# Power.net
KiCad netlist of a schematic drawn in Altium Designer
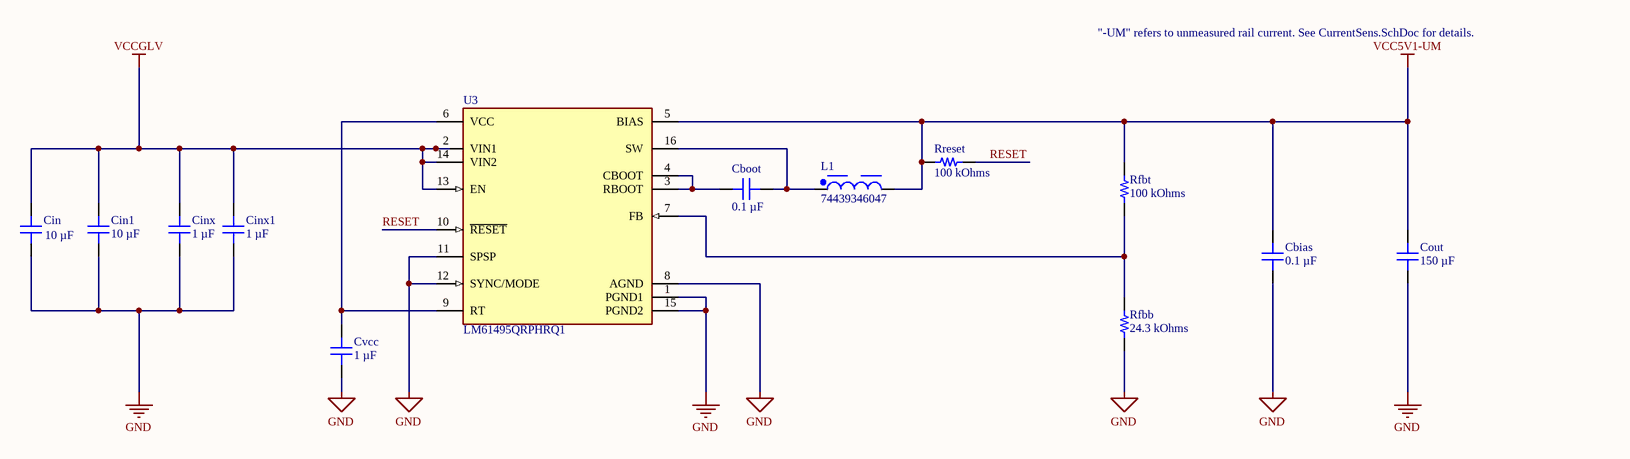
[diagram p0: Power.SchDoc]

(export (version "E")
  (design (tool "Eeschema 10.0.6"))
  (components
    (comp (ref "Cbias")
      (value "0.1 µF")
      (footprint "CAP 0402_1005")
      (description "CAP CER 0.1UF 16V X7R 0402")
      (fields
        (field (name "PART NUMBER") "CL05B104KO5NFNC")
        (field (name "MANUFACTURER") "Samsung Electro-Mechanics")
      )
      (libsource (lib "Celestial Altium Library - altium_library") (part "Capacitor"))
    )
    (comp (ref "Cboot")
      (value "0.1 µF")
      (footprint "CAP 0402_1005")
      (description "CAP CER 0.1UF 10V X7R 0402")
      (fields
        (field (name "PART NUMBER") "CL05B104KP5NNNC")
        (field (name "MANUFACTURER") "Samsung Electro-Mechanics")
      )
      (libsource (lib "Celestial Altium Library - altium_library") (part "Capacitor"))
    )
    (comp (ref "Cin")
      (value "10 µF")
      (footprint "CAP 1210_3225 - 1MM")
      (description "CAP CER 10UF 50V X7R 1210")
      (fields
        (field (name "PART NUMBER") "GRM32ER71H106KA12L")
        (field (name "MANUFACTURER") "Murata Electronics")
      )
      (libsource (lib "Celestial Altium Library - altium_library") (part "Capacitor"))
    )
    (comp (ref "Cin1")
      (value "10 µF")
      (footprint "CAP 1210_3225 - 1MM")
      (description "CAP CER 10UF 50V X7R 1210")
      (fields
        (field (name "PART NUMBER") "GRM32ER71H106KA12L")
        (field (name "MANUFACTURER") "Murata Electronics")
      )
      (libsource (lib "Celestial Altium Library - altium_library") (part "Capacitor"))
    )
    (comp (ref "Cinx")
      (value "1 µF")
      (footprint "CAP 0603_1608")
      (description "CAP CER 1UF 50V X5R 0603")
      (fields
        (field (name "PART NUMBER") "C1608X5R1H105K080AB")
        (field (name "MANUFACTURER") "TDK Corporation")
      )
      (libsource (lib "Celestial Altium Library - altium_library") (part "Capacitor"))
    )
    (comp (ref "Cinx1")
      (value "1 µF")
      (footprint "CAP 0603_1608")
      (description "CAP CER 1UF 50V X5R 0603")
      (fields
        (field (name "PART NUMBER") "C1608X5R1H105K080AB")
        (field (name "MANUFACTURER") "TDK Corporation")
      )
      (libsource (lib "Celestial Altium Library - altium_library") (part "Capacitor"))
    )
    (comp (ref "Cout")
      (value "150 µF")
      (footprint "CAP 1210_3225 - 1MM")
      (description "CAP CER 150UF 6.3V X5R 1210")
      (fields
        (field (name "PART NUMBER") "CL32A157MQVNNNE")
        (field (name "MANUFACTURER") "Samsung Electro-Mechanics")
      )
      (libsource (lib "Celestial Altium Library - altium_library") (part "Capacitor"))
    )
    (comp (ref "Cvcc")
      (value "1 µF")
      (footprint "CAP 0603_1608")
      (description "CAP CER 1UF 6.3V X5R 0603")
      (fields (field (name "PART NUMBER") "KGM15BR50J105KT") (field (name "MANUFACTURER") "KYOCERA AVX"))
      (libsource (lib "Celestial Altium Library - altium_library") (part "Capacitor"))
    )
    (comp (ref "L1")
      (value "74439346047")
      (footprint "WE-XHMI_6060_L6.65W6.45H5.8")
      (description "FIXED IND 4.7UH 7.4A 13 MOHM")
      (fields (field (name "TOLERANCE") "20%"))
      (libsource (lib "Altium Content Vault") (part "Inductor - 2"))
    )
    (comp (ref "Rfbb")
      (value "24.3 kOhms")
      (footprint "RES 0402_1005")
      (description "RES SMD 24.3K OHM 1% 1/16W 0402")
      (fields (field (name "PART NUMBER") "CRCW040224K3FKTD") (field (name "MANUFACTURER") "Vishay Dale"))
      (libsource (lib "Celestial Altium Library - altium_library") (part "Resistor"))
    )
    (comp (ref "Rfbt")
      (value "100 kOhms")
      (footprint "RES 0402_1005")
      (description "RES SMD 100K OHM 1% 1/16W 0402")
      (fields (field (name "PART NUMBER") "CRCW0402100KFKED") (field (name "MANUFACTURER") "Vishay Dale"))
      (libsource (lib "Celestial Altium Library - altium_library") (part "Resistor"))
    )
    (comp (ref "Rreset")
      (value "100 kOhms")
      (footprint "RES 0402_1005")
      (description "RES SMD 100K OHM 1% 1/16W 0402")
      (fields (field (name "PART NUMBER") "CRCW0402100KFKED") (field (name "MANUFACTURER") "Vishay Dale"))
      (libsource (lib "Celestial Altium Library - altium_library") (part "Resistor"))
    )
    (comp (ref "U3")
      (value "LM61495QRPHRQ1")
      (footprint "FP-RPH0016A-MFG")
      (description "10-A automotive buck converter optimized for power density and low EMI 16-VQFN-HR -40 to 150")
      (libsource (lib "Altium Content Vault") (part "31ba6acbc2ffca682b30009bfb1cfc4"))
    )
  )
  (nets
    (net (code "1") (name "/RESET") (class "Default")
      (node (ref "Rreset") (pin "2") (pinfunction "2_2") (pintype "passive"))
      (node (ref "U3") (pin "10") (pinfunction "~{RESET}_10") (pintype "input"))
    )
    (net (code "2") (name "GND") (class "Default")
      (node (ref "Cbias") (pin "1") (pinfunction "1_1") (pintype "passive"))
      (node (ref "Cin") (pin "1") (pinfunction "1_1") (pintype "passive"))
      (node (ref "Cin1") (pin "1") (pinfunction "1_1") (pintype "passive"))
      (node (ref "Cinx") (pin "1") (pinfunction "1_1") (pintype "passive"))
      (node (ref "Cinx1") (pin "1") (pinfunction "1_1") (pintype "passive"))
      (node (ref "Cout") (pin "1") (pinfunction "1_1") (pintype "passive"))
      (node (ref "Cvcc") (pin "1") (pinfunction "1_1") (pintype "passive"))
      (node (ref "Rfbb") (pin "1") (pinfunction "1_1") (pintype "passive"))
      (node (ref "U3") (pin "1") (pinfunction "PGND1_1") (pintype "power_in"))
      (node (ref "U3") (pin "11") (pinfunction "SPSP_11") (pintype "passive"))
      (node (ref "U3") (pin "12") (pinfunction "SYNC/MODE_12") (pintype "input"))
      (node (ref "U3") (pin "15") (pinfunction "PGND2_15") (pintype "power_in"))
      (node (ref "U3") (pin "8") (pinfunction "AGND_8") (pintype "power_in"))
    )
    (net (code "3") (name "Net-(U3-CBOOT)") (class "Default")
      (node (ref "Cboot") (pin "1") (pinfunction "1_1") (pintype "passive"))
      (node (ref "U3") (pin "3") (pinfunction "RBOOT_3") (pintype "passive"))
      (node (ref "U3") (pin "4") (pinfunction "CBOOT_4") (pintype "passive"))
    )
    (net (code "4") (name "Net-(U3-FB)") (class "Default")
      (node (ref "Rfbb") (pin "2") (pinfunction "2_2") (pintype "passive"))
      (node (ref "Rfbt") (pin "1") (pinfunction "1_1") (pintype "passive"))
      (node (ref "U3") (pin "7") (pinfunction "FB_7") (pintype "input"))
    )
    (net (code "5") (name "Net-(U3-RT)") (class "Default")
      (node (ref "Cvcc") (pin "2") (pinfunction "2_2") (pintype "passive"))
      (node (ref "U3") (pin "6") (pinfunction "VCC_6") (pintype "power_in"))
      (node (ref "U3") (pin "9") (pinfunction "RT_9") (pintype "passive"))
    )
    (net (code "6") (name "Net-(U3-SW)") (class "Default")
      (node (ref "Cboot") (pin "2") (pinfunction "2_2") (pintype "passive"))
      (node (ref "L1") (pin "1") (pinfunction "1_1") (pintype "passive"))
      (node (ref "U3") (pin "16") (pinfunction "SW_16") (pintype "power_in"))
    )
    (net (code "7") (name "VCC5V1-UM") (class "Default")
      (node (ref "Cbias") (pin "2") (pinfunction "2_2") (pintype "passive"))
      (node (ref "Cout") (pin "2") (pinfunction "2_2") (pintype "passive"))
      (node (ref "L1") (pin "2") (pinfunction "2_2") (pintype "passive"))
      (node (ref "Rfbt") (pin "2") (pinfunction "2_2") (pintype "passive"))
      (node (ref "Rreset") (pin "1") (pinfunction "1_1") (pintype "passive"))
      (node (ref "U3") (pin "5") (pinfunction "BIAS_5") (pintype "passive"))
    )
    (net (code "8") (name "VCCGLV") (class "Default")
      (node (ref "Cin") (pin "2") (pinfunction "2_2") (pintype "passive"))
      (node (ref "Cin1") (pin "2") (pinfunction "2_2") (pintype "passive"))
      (node (ref "Cinx") (pin "2") (pinfunction "2_2") (pintype "passive"))
      (node (ref "Cinx1") (pin "2") (pinfunction "2_2") (pintype "passive"))
      (node (ref "U3") (pin "13") (pinfunction "EN_13") (pintype "input"))
      (node (ref "U3") (pin "14") (pinfunction "VIN2_14") (pintype "power_in"))
      (node (ref "U3") (pin "2") (pinfunction "VIN1_2") (pintype "power_in"))
    )
  )
)
